# untitled.net
KiCad netlist of a schematic drawn in EAGLE
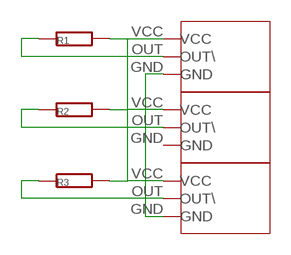
[diagram p0: schematic, sheet 1]

(export (version "E")
  (design (tool "Eeschema 10.0.6"))
  (components
    (comp (ref "R1")
      (value "R0603")
      (footprint "eagle-import:0603")
      (libsource (lib "eagle-import") (part "R0603"))
    )
    (comp (ref "R2")
      (value "R0603")
      (footprint "eagle-import:0603")
      (libsource (lib "eagle-import") (part "R0603"))
    )
    (comp (ref "R3")
      (value "R0603")
      (footprint "eagle-import:0603")
      (libsource (lib "eagle-import") (part "R0603"))
    )
    (comp (ref "U$1")
      (value "HALL")
      (footprint "eagle-import:HALL")
      (libsource (lib "eagle-import") (part "HALL"))
    )
    (comp (ref "U$2")
      (value "HALL")
      (footprint "eagle-import:HALL")
      (libsource (lib "eagle-import") (part "HALL"))
    )
    (comp (ref "U$3")
      (value "HALL")
      (footprint "eagle-import:HALL")
      (libsource (lib "eagle-import") (part "HALL"))
    )
  )
  (nets
    (net (code "1") (name "Net-(R1-Pad2)") (class "Default")
      (node (ref "R1") (pin "2") (pinfunction "2_2") (pintype "passive"))
      (node (ref "R2") (pin "2") (pinfunction "2_2") (pintype "passive"))
      (node (ref "R3") (pin "2") (pinfunction "2_2") (pintype "passive"))
      (node (ref "U$1") (pin "VCC") (pinfunction "VCC_VCC") (pintype "bidirectional"))
      (node (ref "U$2") (pin "VCC") (pinfunction "VCC_VCC") (pintype "bidirectional"))
      (node (ref "U$3") (pin "VCC") (pinfunction "VCC_VCC") (pintype "bidirectional"))
    )
    (net (code "2") (name "Net-(U$1-OUT\\)") (class "Default")
      (node (ref "R1") (pin "1") (pinfunction "1_1") (pintype "passive"))
      (node (ref "U$1") (pin "OUT") (pinfunction "OUT\\_OUT") (pintype "bidirectional"))
    )
    (net (code "3") (name "Net-(U$1-PadGND)") (class "Default")
      (node (ref "U$1") (pin "GND") (pinfunction "GND_GND") (pintype "bidirectional"))
      (node (ref "U$3") (pin "GND") (pinfunction "GND_GND") (pintype "bidirectional"))
    )
    (net (code "4") (name "Net-(U$2-OUT\\)") (class "Default")
      (node (ref "R2") (pin "1") (pinfunction "1_1") (pintype "passive"))
      (node (ref "U$2") (pin "OUT") (pinfunction "OUT\\_OUT") (pintype "bidirectional"))
    )
    (net (code "5") (name "Net-(U$3-OUT\\)") (class "Default")
      (node (ref "R3") (pin "1") (pinfunction "1_1") (pintype "passive"))
      (node (ref "U$3") (pin "OUT") (pinfunction "OUT\\_OUT") (pintype "bidirectional"))
    )
    (net (code "6") (name "unconnected-(U$2-PadGND)") (class "Default")
      (node (ref "U$2") (pin "GND") (pinfunction "GND_GND") (pintype "bidirectional"))
    )
  )
)
